# Pi2RMini_2_0.net
KiCad netlist of a schematic drawn in EAGLE
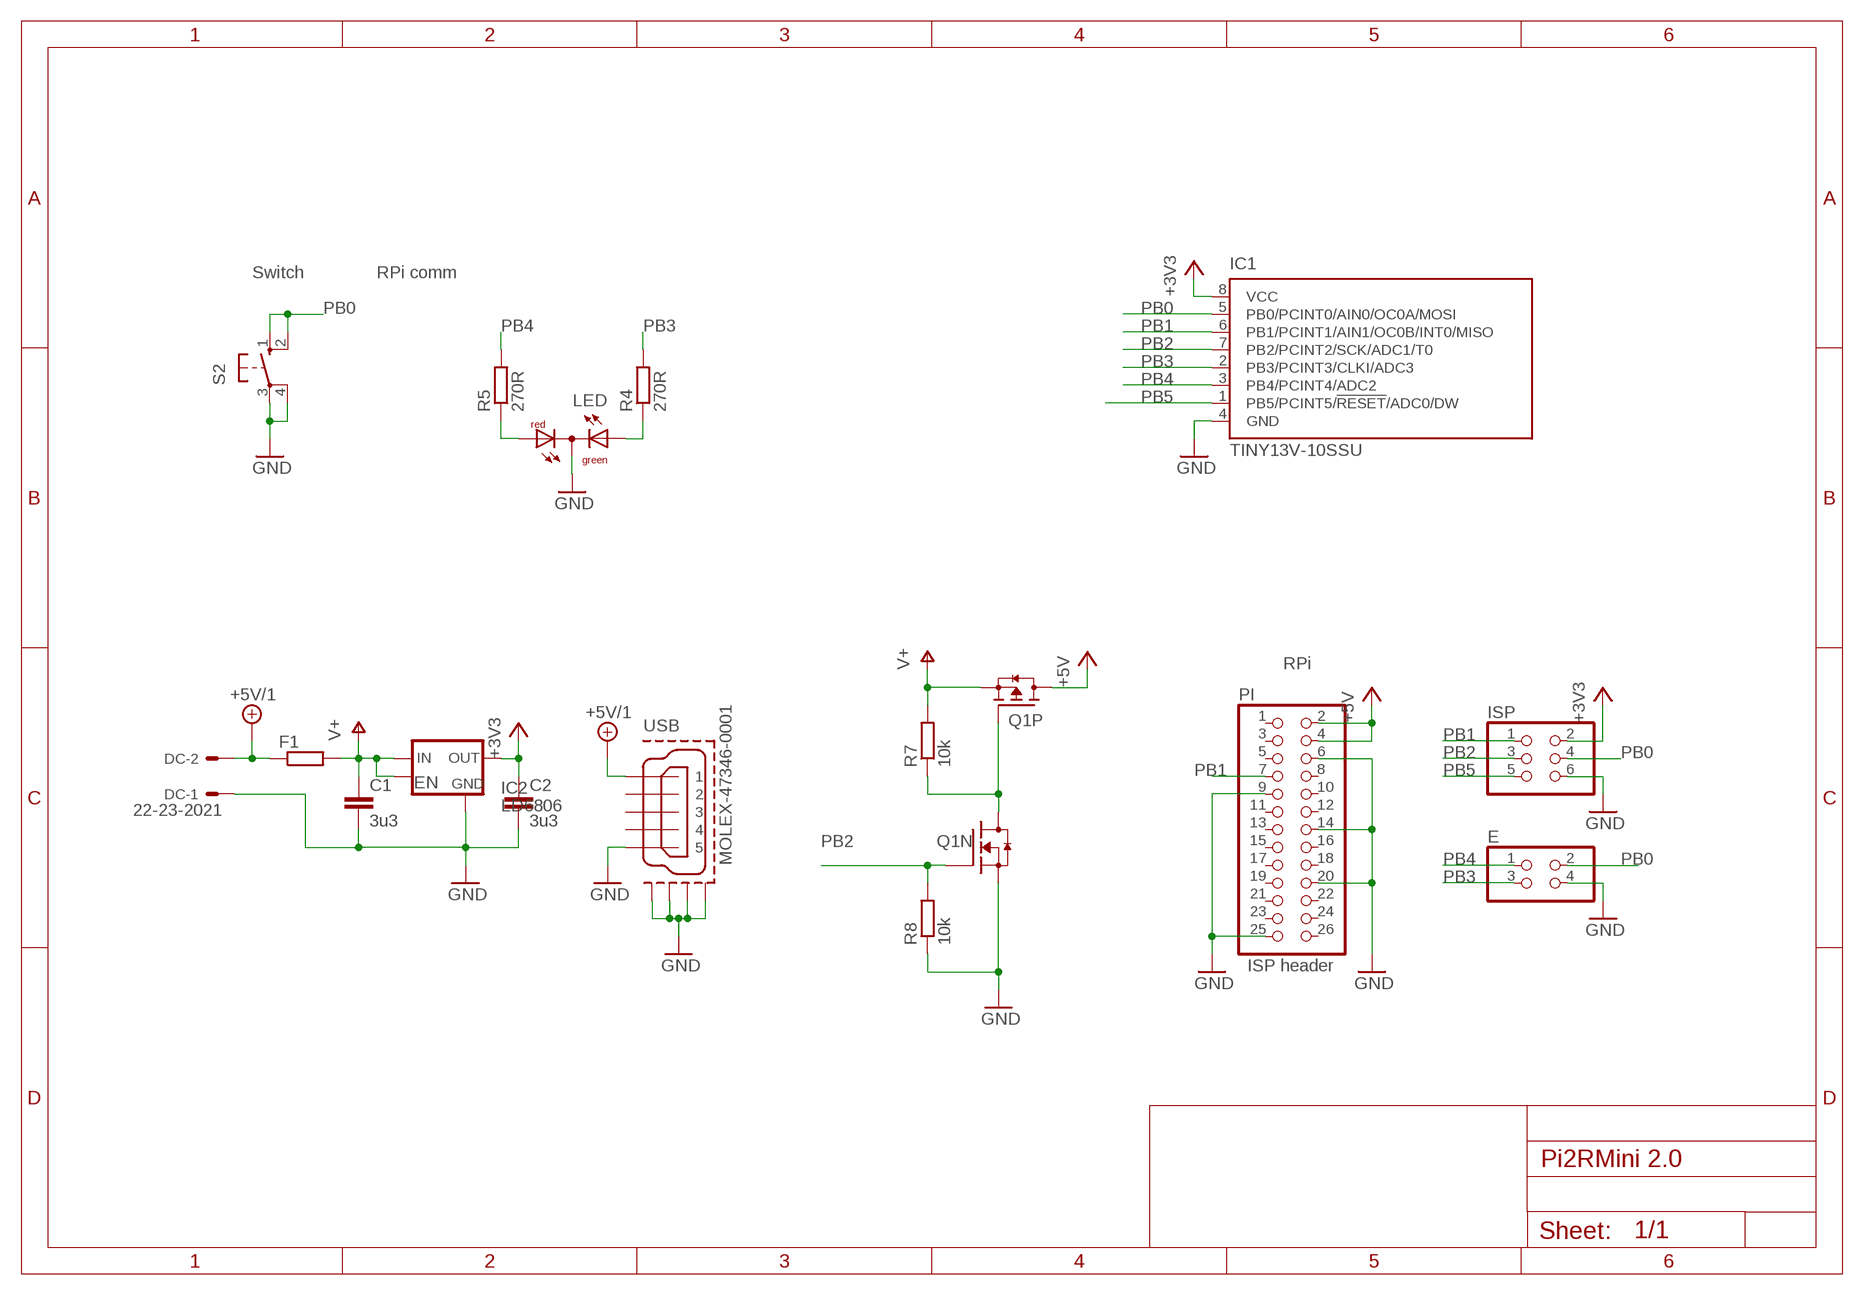
[diagram p0: schematic, sheet 1]

(export (version "E")
  (design (tool "Eeschema 10.0.6"))
  (components
    (comp (ref "C1")
      (value "3u3")
      (footprint "eagle-import:C0603")
      (libsource (lib "eagle-import") (part "C-EUC0603"))
    )
    (comp (ref "C2")
      (value "3u3")
      (footprint "eagle-import:C0603")
      (libsource (lib "eagle-import") (part "C-EUC0603"))
    )
    (comp (ref "DC")
      (value "22-23-2021")
      (footprint "eagle-import:22-23-2021")
      (fields (field (name "MF") "MOLEX"))
      (libsource (lib "eagle-import") (part "22-23-2021"))
    )
    (comp (ref "E")
      (value "PINHD-2X2")
      (footprint "eagle-import:2X02")
      (libsource (lib "eagle-import") (part "PINHD-2X2"))
    )
    (comp (ref "F1")
      (value "R-EU_R1210")
      (footprint "eagle-import:R1210")
      (libsource (lib "eagle-import") (part "R-EU_R1210"))
    )
    (comp (ref "IC1")
      (value "TINY13V-10SSU")
      (footprint "eagle-import:8S1")
      (fields (field (name "MPN") "ATTINY13V-10SSU"))
      (libsource (lib "eagle-import") (part "TINY13SSUV-10"))
    )
    (comp (ref "IC2")
      (value "LD6806")
      (footprint "eagle-import:SOT-753")
      (libsource (lib "eagle-import") (part "LD6806"))
    )
    (comp (ref "ISP")
      (value "PINHD-2X3")
      (footprint "eagle-import:2X03")
      (libsource (lib "eagle-import") (part "PINHD-2X3"))
    )
    (comp (ref "LED")
      (value "DUOLED-CC")
      (footprint "eagle-import:SOT-23")
      (libsource (lib "eagle-import") (part "DUOLED-CC"))
    )
    (comp (ref "PI")
      (value "PINHD-2X13")
      (footprint "eagle-import:2X13")
      (libsource (lib "eagle-import") (part "PINHD-2X13"))
    )
    (comp (ref "Q1")
      (value "BSL215")
      (footprint "eagle-import:6TSOP")
      (libsource (lib "eagle-import") (part "BSL215"))
    )
    (comp (ref "R4")
      (value "270R")
      (footprint "eagle-import:R0603")
      (libsource (lib "eagle-import") (part "R-EU_R0603"))
    )
    (comp (ref "R5")
      (value "270R")
      (footprint "eagle-import:R0603")
      (libsource (lib "eagle-import") (part "R-EU_R0603"))
    )
    (comp (ref "R7")
      (value "10k")
      (footprint "eagle-import:R0603")
      (libsource (lib "eagle-import") (part "R-EU_R0603"))
    )
    (comp (ref "R8")
      (value "10k")
      (footprint "eagle-import:R0603")
      (libsource (lib "eagle-import") (part "R-EU_R0603"))
    )
    (comp (ref "S2")
      (value "10-XX")
      (footprint "eagle-import:B3F-10XX")
      (fields (field (name "MPN") "B3F-1000"))
      (libsource (lib "eagle-import") (part "10-XX"))
    )
    (comp (ref "USB")
      (value "MOLEX-47346-0001")
      (footprint "eagle-import:MOLEX-47364-0001")
      (libsource (lib "eagle-import") (part "MOLEX-47346-0001"))
    )
  )
  (nets
    (net (code "1") (name "+3V3") (class "Default")
      (node (ref "C2") (pin "1") (pinfunction "1_1") (pintype "passive"))
      (node (ref "IC1") (pin "8") (pinfunction "VCC_8") (pintype "power_in"))
      (node (ref "IC2") (pin "5") (pinfunction "OUT_5") (pintype "power_in"))
      (node (ref "ISP") (pin "2") (pinfunction "2_2") (pintype "passive"))
    )
    (net (code "2") (name "+5V") (class "Default")
      (node (ref "PI") (pin "2") (pinfunction "2_2") (pintype "passive"))
      (node (ref "PI") (pin "4") (pinfunction "4_4") (pintype "passive"))
      (node (ref "Q1") (pin "4") (pinfunction "D_4") (pintype "passive"))
    )
    (net (code "3") (name "+5V{slash}1") (class "Default")
      (node (ref "DC") (pin "2") (pinfunction "S_2") (pintype "passive"))
      (node (ref "F1") (pin "1") (pinfunction "1_1") (pintype "passive"))
      (node (ref "USB") (pin "1") (pinfunction "1_1") (pintype "input"))
    )
    (net (code "4") (name "/PB0") (class "Default")
      (node (ref "E") (pin "2") (pinfunction "2_2") (pintype "passive"))
      (node (ref "IC1") (pin "5") (pinfunction "PB0/PCINT0/AIN0/OC0A/MOSI_5") (pintype "bidirectional"))
      (node (ref "ISP") (pin "4") (pinfunction "4_4") (pintype "passive"))
      (node (ref "S2") (pin "1") (pinfunction "S_1") (pintype "passive"))
      (node (ref "S2") (pin "2") (pinfunction "S1_2") (pintype "passive"))
    )
    (net (code "5") (name "/PB1") (class "Default")
      (node (ref "IC1") (pin "6") (pinfunction "PB1/PCINT1/AIN1/OC0B/INT0/MISO_6") (pintype "bidirectional"))
      (node (ref "ISP") (pin "1") (pinfunction "1_1") (pintype "passive"))
      (node (ref "PI") (pin "7") (pinfunction "7_7") (pintype "passive"))
    )
    (net (code "6") (name "/PB2") (class "Default")
      (node (ref "IC1") (pin "7") (pinfunction "PB2/PCINT2/SCK/ADC1/T0_7") (pintype "bidirectional"))
      (node (ref "ISP") (pin "3") (pinfunction "3_3") (pintype "passive"))
      (node (ref "Q1") (pin "1") (pinfunction "G_1") (pintype "passive"))
      (node (ref "R8") (pin "2") (pinfunction "2_2") (pintype "passive"))
    )
    (net (code "7") (name "/PB3") (class "Default")
      (node (ref "E") (pin "3") (pinfunction "3_3") (pintype "passive"))
      (node (ref "IC1") (pin "2") (pinfunction "PB3/PCINT3/CLKI/ADC3_2") (pintype "bidirectional"))
      (node (ref "R4") (pin "2") (pinfunction "2_2") (pintype "passive"))
    )
    (net (code "8") (name "/PB4") (class "Default")
      (node (ref "E") (pin "1") (pinfunction "1_1") (pintype "passive"))
      (node (ref "IC1") (pin "3") (pinfunction "PB4/PCINT4/ADC2_3") (pintype "bidirectional"))
      (node (ref "R5") (pin "2") (pinfunction "2_2") (pintype "passive"))
    )
    (net (code "9") (name "/PB5") (class "Default")
      (node (ref "IC1") (pin "1") (pinfunction "PB5/PCINT5/~{RESET}/ADC0/DW_1") (pintype "bidirectional"))
      (node (ref "ISP") (pin "5") (pinfunction "5_5") (pintype "passive"))
    )
    (net (code "10") (name "GND") (class "Default")
      (node (ref "C1") (pin "2") (pinfunction "2_2") (pintype "passive"))
      (node (ref "C2") (pin "2") (pinfunction "2_2") (pintype "passive"))
      (node (ref "DC") (pin "1") (pinfunction "S_1") (pintype "passive"))
      (node (ref "E") (pin "4") (pinfunction "4_4") (pintype "passive"))
      (node (ref "IC1") (pin "4") (pinfunction "GND_4") (pintype "power_in"))
      (node (ref "IC2") (pin "2") (pinfunction "GND_2") (pintype "power_in"))
      (node (ref "ISP") (pin "6") (pinfunction "6_6") (pintype "passive"))
      (node (ref "LED") (pin "3") (pinfunction "C_3") (pintype "passive"))
      (node (ref "PI") (pin "14") (pinfunction "14_14") (pintype "passive"))
      (node (ref "PI") (pin "20") (pinfunction "20_20") (pintype "passive"))
      (node (ref "PI") (pin "25") (pinfunction "25_25") (pintype "passive"))
      (node (ref "PI") (pin "6") (pinfunction "6_6") (pintype "passive"))
      (node (ref "PI") (pin "9") (pinfunction "9_9") (pintype "passive"))
      (node (ref "Q1") (pin "5") (pinfunction "S_5") (pintype "passive"))
      (node (ref "R8") (pin "1") (pinfunction "1_1") (pintype "passive"))
      (node (ref "S2") (pin "3") (pinfunction "P_3") (pintype "passive"))
      (node (ref "S2") (pin "4") (pinfunction "P1_4") (pintype "passive"))
      (node (ref "USB") (pin "5") (pinfunction "5_5") (pintype "input"))
      (node (ref "USB") (pin "GND1") (pinfunction "GND1_GND1") (pintype "bidirectional"))
      (node (ref "USB") (pin "GND2") (pinfunction "GND2_GND2") (pintype "bidirectional"))
      (node (ref "USB") (pin "GND3") (pinfunction "GND3_GND3") (pintype "bidirectional"))
      (node (ref "USB") (pin "GND4") (pinfunction "GND4_GND4") (pintype "bidirectional"))
    )
    (net (code "11") (name "Net-(LED-AG)") (class "Default")
      (node (ref "LED") (pin "2") (pinfunction "AG_2") (pintype "passive"))
      (node (ref "R4") (pin "1") (pinfunction "1_1") (pintype "passive"))
    )
    (net (code "12") (name "Net-(LED-AR)") (class "Default")
      (node (ref "LED") (pin "1") (pinfunction "AR_1") (pintype "passive"))
      (node (ref "R5") (pin "1") (pinfunction "1_1") (pintype "passive"))
    )
    (net (code "13") (name "Net-(Q1A-D)") (class "Default")
      (node (ref "Q1") (pin "3") (pinfunction "G_3") (pintype "passive"))
      (node (ref "Q1") (pin "6") (pinfunction "D_6") (pintype "passive"))
      (node (ref "R7") (pin "1") (pinfunction "1_1") (pintype "passive"))
    )
    (net (code "14") (name "V+") (class "Default")
      (node (ref "C1") (pin "1") (pinfunction "1_1") (pintype "passive"))
      (node (ref "F1") (pin "2") (pinfunction "2_2") (pintype "passive"))
      (node (ref "IC2") (pin "1") (pinfunction "IN_1") (pintype "power_in"))
      (node (ref "IC2") (pin "3") (pinfunction "EN_3") (pintype "power_in"))
      (node (ref "Q1") (pin "2") (pinfunction "S_2") (pintype "passive"))
      (node (ref "R7") (pin "2") (pinfunction "2_2") (pintype "passive"))
    )
    (net (code "15") (name "unconnected-(PI-Pad1)") (class "Default")
      (node (ref "PI") (pin "1") (pinfunction "1_1") (pintype "passive"))
    )
    (net (code "16") (name "unconnected-(PI-Pad3)") (class "Default")
      (node (ref "PI") (pin "3") (pinfunction "3_3") (pintype "passive"))
    )
    (net (code "17") (name "unconnected-(PI-Pad5)") (class "Default")
      (node (ref "PI") (pin "5") (pinfunction "5_5") (pintype "passive"))
    )
    (net (code "18") (name "unconnected-(PI-Pad8)") (class "Default")
      (node (ref "PI") (pin "8") (pinfunction "8_8") (pintype "passive"))
    )
    (net (code "19") (name "unconnected-(PI-Pad10)") (class "Default")
      (node (ref "PI") (pin "10") (pinfunction "10_10") (pintype "passive"))
    )
    (net (code "20") (name "unconnected-(PI-Pad11)") (class "Default")
      (node (ref "PI") (pin "11") (pinfunction "11_11") (pintype "passive"))
    )
    (net (code "21") (name "unconnected-(PI-Pad12)") (class "Default")
      (node (ref "PI") (pin "12") (pinfunction "12_12") (pintype "passive"))
    )
    (net (code "22") (name "unconnected-(PI-Pad13)") (class "Default")
      (node (ref "PI") (pin "13") (pinfunction "13_13") (pintype "passive"))
    )
    (net (code "23") (name "unconnected-(PI-Pad15)") (class "Default")
      (node (ref "PI") (pin "15") (pinfunction "15_15") (pintype "passive"))
    )
    (net (code "24") (name "unconnected-(PI-Pad16)") (class "Default")
      (node (ref "PI") (pin "16") (pinfunction "16_16") (pintype "passive"))
    )
    (net (code "25") (name "unconnected-(PI-Pad17)") (class "Default")
      (node (ref "PI") (pin "17") (pinfunction "17_17") (pintype "passive"))
    )
    (net (code "26") (name "unconnected-(PI-Pad18)") (class "Default")
      (node (ref "PI") (pin "18") (pinfunction "18_18") (pintype "passive"))
    )
    (net (code "27") (name "unconnected-(PI-Pad19)") (class "Default")
      (node (ref "PI") (pin "19") (pinfunction "19_19") (pintype "passive"))
    )
    (net (code "28") (name "unconnected-(PI-Pad21)") (class "Default")
      (node (ref "PI") (pin "21") (pinfunction "21_21") (pintype "passive"))
    )
    (net (code "29") (name "unconnected-(PI-Pad22)") (class "Default")
      (node (ref "PI") (pin "22") (pinfunction "22_22") (pintype "passive"))
    )
    (net (code "30") (name "unconnected-(PI-Pad23)") (class "Default")
      (node (ref "PI") (pin "23") (pinfunction "23_23") (pintype "passive"))
    )
    (net (code "31") (name "unconnected-(PI-Pad24)") (class "Default")
      (node (ref "PI") (pin "24") (pinfunction "24_24") (pintype "passive"))
    )
    (net (code "32") (name "unconnected-(PI-Pad26)") (class "Default")
      (node (ref "PI") (pin "26") (pinfunction "26_26") (pintype "passive"))
    )
    (net (code "33") (name "unconnected-(USB-Pad2)") (class "Default")
      (node (ref "USB") (pin "2") (pinfunction "2_2") (pintype "input"))
    )
    (net (code "34") (name "unconnected-(USB-Pad3)") (class "Default")
      (node (ref "USB") (pin "3") (pinfunction "3_3") (pintype "input"))
    )
    (net (code "35") (name "unconnected-(USB-Pad4)") (class "Default")
      (node (ref "USB") (pin "4") (pinfunction "4_4") (pintype "input"))
    )
  )
)
